# Adafruit_OLED_128x32_Mono_I2C.net
KiCad netlist of a schematic drawn in EAGLE
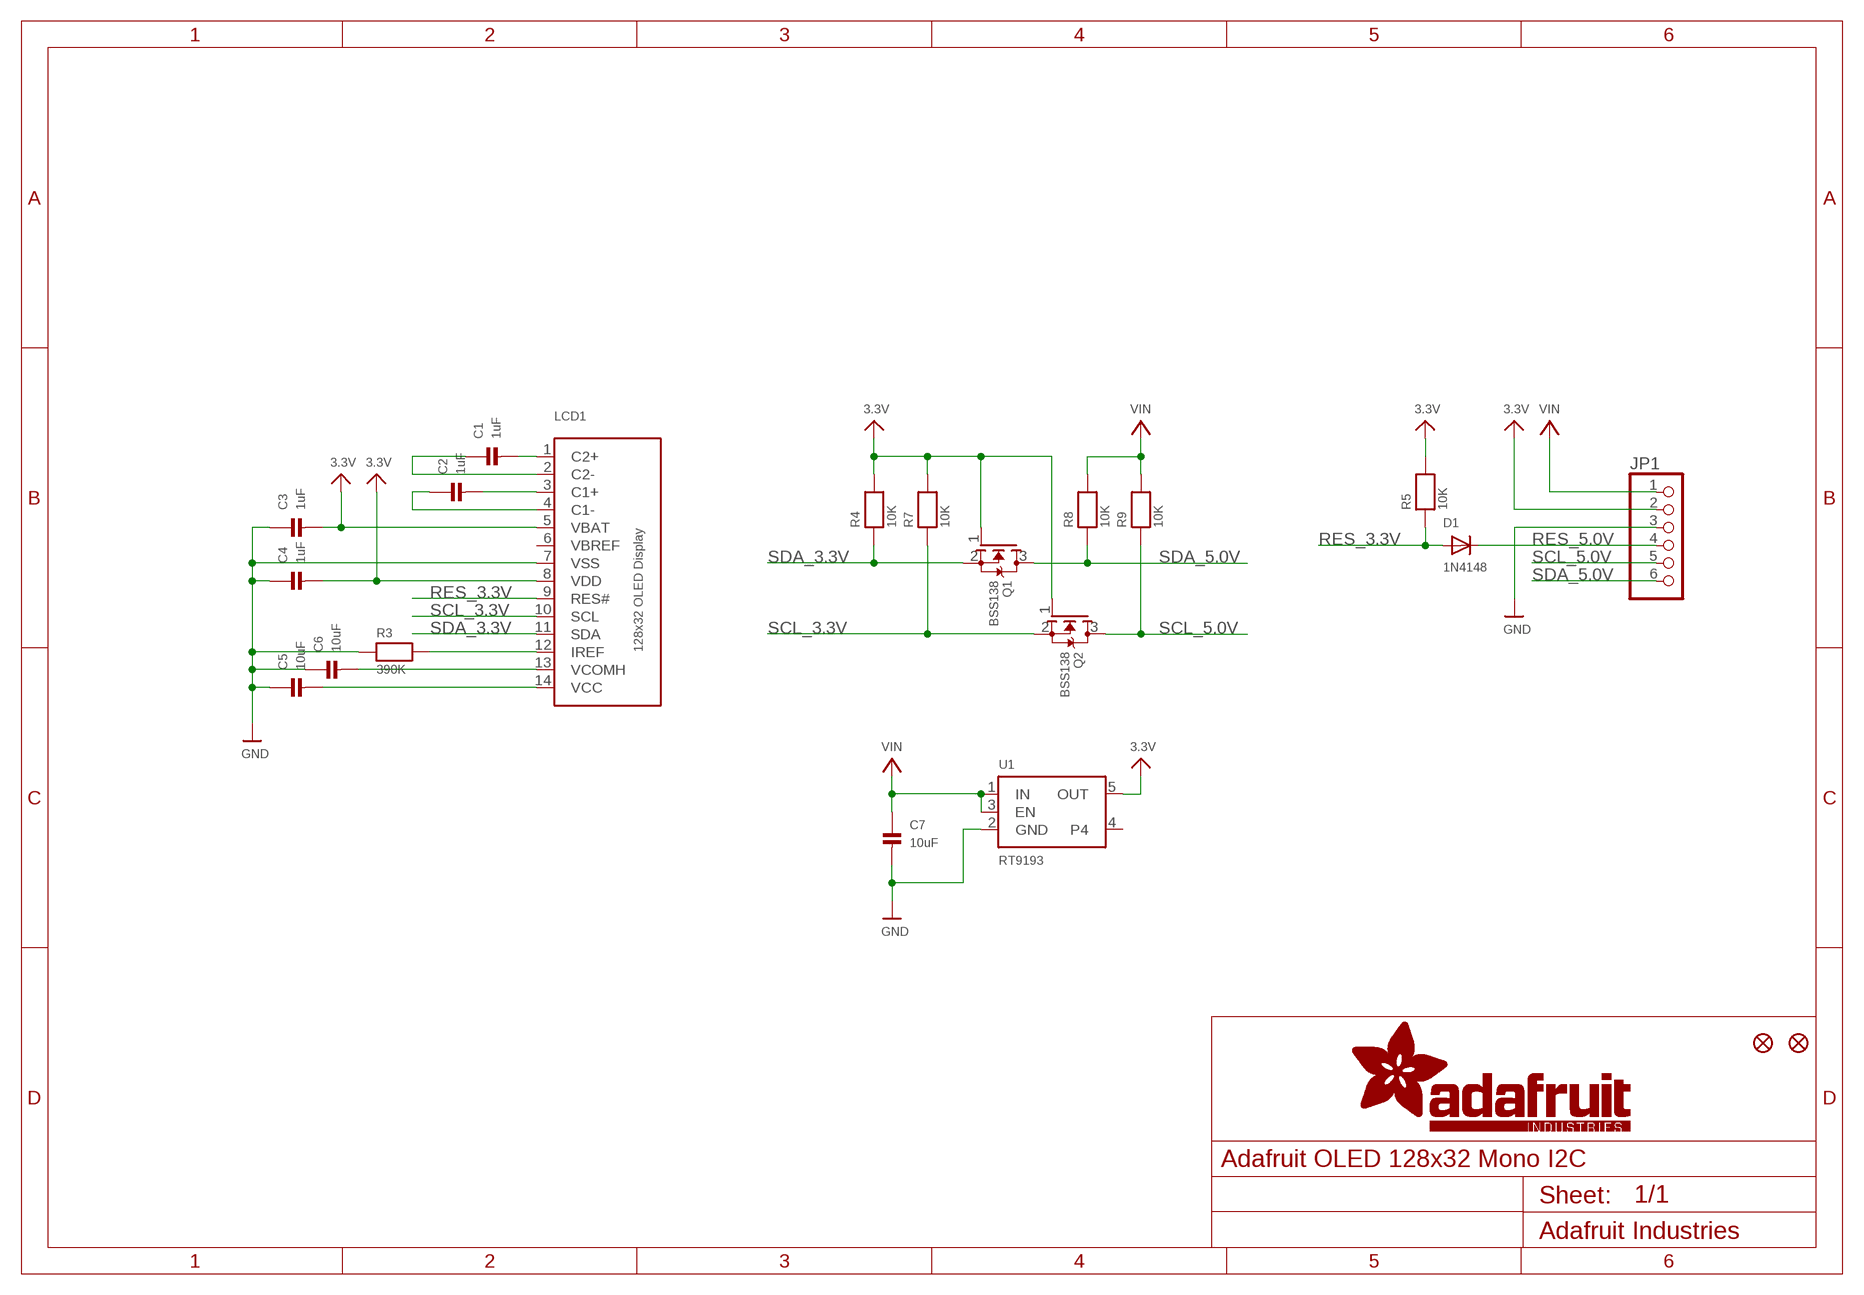
[diagram p0: schematic, sheet 1]

(export (version "E")
  (design (tool "Eeschema 10.0.6"))
  (components
    (comp (ref "C1")
      (value "1uF")
      (footprint "eagle-import:0805")
      (libsource (lib "eagle-import") (part "CAP_CERAMIC0805"))
    )
    (comp (ref "C2")
      (value "1uF")
      (footprint "eagle-import:0805")
      (libsource (lib "eagle-import") (part "CAP_CERAMIC0805"))
    )
    (comp (ref "C3")
      (value "1uF")
      (footprint "eagle-import:0805")
      (libsource (lib "eagle-import") (part "CAP_CERAMIC0805"))
    )
    (comp (ref "C4")
      (value "1uF")
      (footprint "eagle-import:0805")
      (libsource (lib "eagle-import") (part "CAP_CERAMIC0805"))
    )
    (comp (ref "C5")
      (value "10uF")
      (footprint "eagle-import:0805")
      (libsource (lib "eagle-import") (part "CAP_CERAMIC0805"))
    )
    (comp (ref "C6")
      (value "10uF")
      (footprint "eagle-import:0805")
      (libsource (lib "eagle-import") (part "CAP_CERAMIC0805"))
    )
    (comp (ref "C7")
      (value "10uF")
      (footprint "eagle-import:0805")
      (libsource (lib "eagle-import") (part "CAP_CERAMIC0805"))
    )
    (comp (ref "D1")
      (value "1N4148")
      (footprint "eagle-import:SOD-323F")
      (libsource (lib "eagle-import") (part "DIODESOD-323F"))
    )
    (comp (ref "FID1")
      (value "FIDUCIAL\"\"")
      (footprint "eagle-import:FIDUCIAL_1MM")
      (libsource (lib "eagle-import") (part "FIDUCIAL{dblquote}{dblquote}"))
    )
    (comp (ref "FID2")
      (value "FIDUCIAL\"\"")
      (footprint "eagle-import:FIDUCIAL_1MM")
      (libsource (lib "eagle-import") (part "FIDUCIAL{dblquote}{dblquote}"))
    )
    (comp (ref "JP1")
      (value "HEADER-1X670MIL")
      (footprint "eagle-import:1X06_ROUND_70")
      (libsource (lib "eagle-import") (part "HEADER-1X670MIL"))
    )
    (comp (ref "LCD1")
      (value "DISP_OLED_UG-2832HSWEG02")
      (footprint "eagle-import:UG-2832HSWEG02_WRAPUNDER")
      (libsource (lib "eagle-import") (part "DISP_OLED_UG-2832HSWEG02"))
    )
    (comp (ref "Q1")
      (value "BSS138")
      (footprint "eagle-import:SOT23-WIDE")
      (libsource (lib "eagle-import") (part "MOSFET-NWIDE"))
    )
    (comp (ref "Q2")
      (value "BSS138")
      (footprint "eagle-import:SOT23-WIDE")
      (libsource (lib "eagle-import") (part "MOSFET-NWIDE"))
    )
    (comp (ref "R3")
      (value "390K")
      (footprint "eagle-import:0805")
      (libsource (lib "eagle-import") (part "RESISTOR0805"))
    )
    (comp (ref "R4")
      (value "10K")
      (footprint "eagle-import:0805")
      (libsource (lib "eagle-import") (part "RESISTOR0805"))
    )
    (comp (ref "R5")
      (value "10K")
      (footprint "eagle-import:0805")
      (libsource (lib "eagle-import") (part "RESISTOR0805"))
    )
    (comp (ref "R7")
      (value "10K")
      (footprint "eagle-import:0805")
      (libsource (lib "eagle-import") (part "RESISTOR0805"))
    )
    (comp (ref "R8")
      (value "10K")
      (footprint "eagle-import:0805")
      (libsource (lib "eagle-import") (part "RESISTOR0805"))
    )
    (comp (ref "R9")
      (value "10K")
      (footprint "eagle-import:0805")
      (libsource (lib "eagle-import") (part "RESISTOR0805"))
    )
    (comp (ref "U1")
      (value "RT9193")
      (footprint "eagle-import:SOT23-5")
      (libsource (lib "eagle-import") (part "VREG_SOT23-5"))
    )
  )
  (nets
    (net (code "1") (name "/RES_3.3V") (class "Default")
      (node (ref "D1") (pin "A") (pinfunction "A_A") (pintype "passive"))
      (node (ref "LCD1") (pin "9") (pinfunction "RES#_9") (pintype "bidirectional"))
      (node (ref "R5") (pin "1") (pinfunction "1_1") (pintype "passive"))
    )
    (net (code "2") (name "/RES_5.0V") (class "Default")
      (node (ref "D1") (pin "C") (pinfunction "C_C") (pintype "passive"))
      (node (ref "JP1") (pin "4") (pinfunction "4_4") (pintype "passive"))
    )
    (net (code "3") (name "/SCL_3.3V") (class "Default")
      (node (ref "LCD1") (pin "10") (pinfunction "SCL_10") (pintype "bidirectional"))
      (node (ref "Q2") (pin "2") (pinfunction "S_2") (pintype "bidirectional"))
      (node (ref "R7") (pin "1") (pinfunction "1_1") (pintype "passive"))
    )
    (net (code "4") (name "/SCL_5.0V") (class "Default")
      (node (ref "JP1") (pin "5") (pinfunction "5_5") (pintype "passive"))
      (node (ref "Q2") (pin "3") (pinfunction "D_3") (pintype "bidirectional"))
      (node (ref "R9") (pin "1") (pinfunction "1_1") (pintype "passive"))
    )
    (net (code "5") (name "/SDA_3.3V") (class "Default")
      (node (ref "LCD1") (pin "11") (pinfunction "SDA_11") (pintype "bidirectional"))
      (node (ref "Q1") (pin "2") (pinfunction "S_2") (pintype "bidirectional"))
      (node (ref "R4") (pin "1") (pinfunction "1_1") (pintype "passive"))
    )
    (net (code "6") (name "/SDA_5.0V") (class "Default")
      (node (ref "JP1") (pin "6") (pinfunction "6_6") (pintype "passive"))
      (node (ref "Q1") (pin "3") (pinfunction "D_3") (pintype "bidirectional"))
      (node (ref "R8") (pin "1") (pinfunction "1_1") (pintype "passive"))
    )
    (net (code "7") (name "/VBREF") (class "Default")
      (node (ref "LCD1") (pin "6") (pinfunction "VBREF_6") (pintype "power_in"))
    )
    (net (code "8") (name "3.3V") (class "Default")
      (node (ref "C3") (pin "2") (pinfunction "P$2_2") (pintype "passive"))
      (node (ref "C4") (pin "2") (pinfunction "P$2_2") (pintype "passive"))
      (node (ref "JP1") (pin "2") (pinfunction "2_2") (pintype "passive"))
      (node (ref "LCD1") (pin "5") (pinfunction "VBAT_5") (pintype "power_in"))
      (node (ref "LCD1") (pin "8") (pinfunction "VDD_8") (pintype "power_in"))
      (node (ref "Q1") (pin "1") (pinfunction "G_1") (pintype "bidirectional"))
      (node (ref "Q2") (pin "1") (pinfunction "G_1") (pintype "bidirectional"))
      (node (ref "R4") (pin "2") (pinfunction "2_2") (pintype "passive"))
      (node (ref "R5") (pin "2") (pinfunction "2_2") (pintype "passive"))
      (node (ref "R7") (pin "2") (pinfunction "2_2") (pintype "passive"))
      (node (ref "U1") (pin "5") (pinfunction "OUT_5") (pintype "bidirectional"))
    )
    (net (code "9") (name "GND") (class "Default")
      (node (ref "C3") (pin "1") (pinfunction "P$1_1") (pintype "passive"))
      (node (ref "C4") (pin "1") (pinfunction "P$1_1") (pintype "passive"))
      (node (ref "C5") (pin "1") (pinfunction "P$1_1") (pintype "passive"))
      (node (ref "C6") (pin "1") (pinfunction "P$1_1") (pintype "passive"))
      (node (ref "C7") (pin "2") (pinfunction "P$2_2") (pintype "passive"))
      (node (ref "JP1") (pin "3") (pinfunction "3_3") (pintype "passive"))
      (node (ref "LCD1") (pin "7") (pinfunction "VSS_7") (pintype "power_in"))
      (node (ref "R3") (pin "1") (pinfunction "1_1") (pintype "passive"))
      (node (ref "U1") (pin "2") (pinfunction "GND_2") (pintype "bidirectional"))
    )
    (net (code "10") (name "Net-(C1-P$1)") (class "Default")
      (node (ref "C1") (pin "1") (pinfunction "P$1_1") (pintype "passive"))
      (node (ref "LCD1") (pin "2") (pinfunction "C2-_2") (pintype "bidirectional"))
    )
    (net (code "11") (name "Net-(C1-P$2)") (class "Default")
      (node (ref "C1") (pin "2") (pinfunction "P$2_2") (pintype "passive"))
      (node (ref "LCD1") (pin "1") (pinfunction "C2+_1") (pintype "bidirectional"))
    )
    (net (code "12") (name "Net-(C2-P$1)") (class "Default")
      (node (ref "C2") (pin "1") (pinfunction "P$1_1") (pintype "passive"))
      (node (ref "LCD1") (pin "4") (pinfunction "C1-_4") (pintype "bidirectional"))
    )
    (net (code "13") (name "Net-(C2-P$2)") (class "Default")
      (node (ref "C2") (pin "2") (pinfunction "P$2_2") (pintype "passive"))
      (node (ref "LCD1") (pin "3") (pinfunction "C1+_3") (pintype "bidirectional"))
    )
    (net (code "14") (name "Net-(C5-P$2)") (class "Default")
      (node (ref "C5") (pin "2") (pinfunction "P$2_2") (pintype "passive"))
      (node (ref "LCD1") (pin "14") (pinfunction "VCC_14") (pintype "power_in"))
    )
    (net (code "15") (name "Net-(C6-P$2)") (class "Default")
      (node (ref "C6") (pin "2") (pinfunction "P$2_2") (pintype "passive"))
      (node (ref "LCD1") (pin "13") (pinfunction "VCOMH_13") (pintype "power_in"))
    )
    (net (code "16") (name "Net-(LCD1-IREF)") (class "Default")
      (node (ref "LCD1") (pin "12") (pinfunction "IREF_12") (pintype "bidirectional"))
      (node (ref "R3") (pin "2") (pinfunction "2_2") (pintype "passive"))
    )
    (net (code "17") (name "VIN") (class "Default")
      (node (ref "C7") (pin "1") (pinfunction "P$1_1") (pintype "passive"))
      (node (ref "JP1") (pin "1") (pinfunction "1_1") (pintype "passive"))
      (node (ref "R8") (pin "2") (pinfunction "2_2") (pintype "passive"))
      (node (ref "R9") (pin "2") (pinfunction "2_2") (pintype "passive"))
      (node (ref "U1") (pin "1") (pinfunction "IN_1") (pintype "bidirectional"))
      (node (ref "U1") (pin "3") (pinfunction "EN_3") (pintype "bidirectional"))
    )
    (net (code "18") (name "unconnected-(U1-P4-Pad4)") (class "Default")
      (node (ref "U1") (pin "4") (pinfunction "P4_4") (pintype "bidirectional"))
    )
  )
)
